# PowerFull_car_engineSteering.net
KiCad netlist of a schematic drawn in Altium Designer
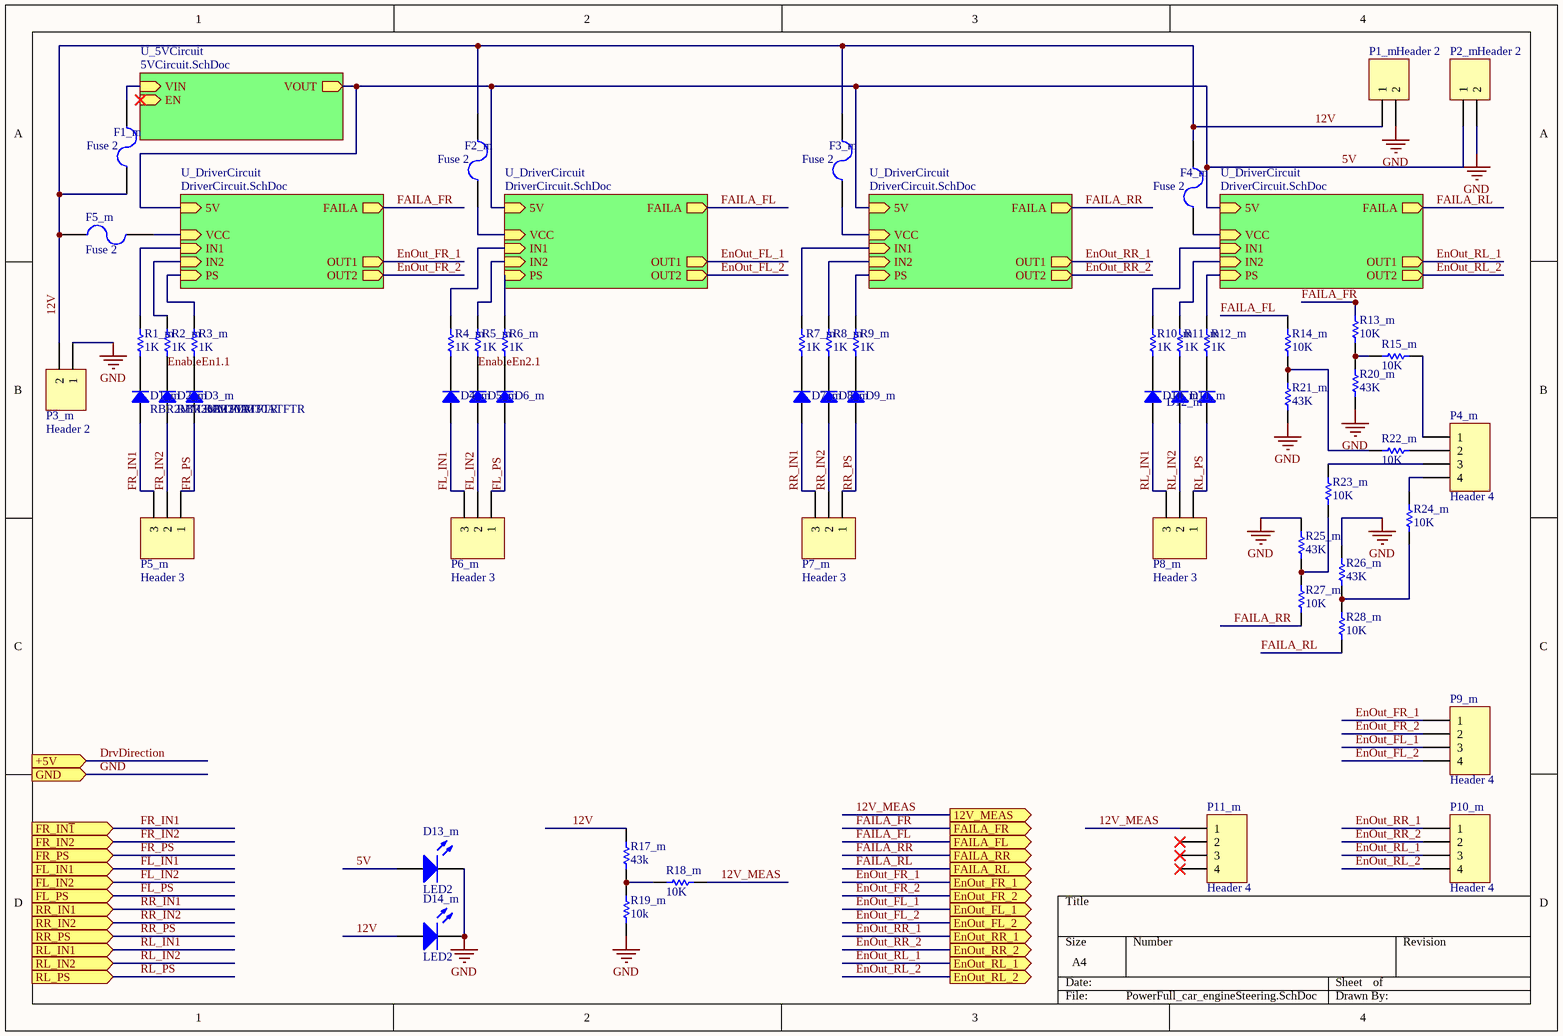
[diagram p0: PowerFull_car_engineSteering.SchDoc]

(export (version "E")
  (design (tool "Eeschema 10.0.6"))
  (components
    (comp (ref "D1_m")
      (value "RBR2MM30ATFTR")
      (footprint "SOD123F")
      (description "DIODE (RECTIFIER FRD) 30V-VR 2A-")
      (fields (field (name "MANUFACTURER") "Rohm Semiconductor"))
      (libsource (lib "Celestial Altium Library - altium_library (5)") (part "Diode"))
    )
    (comp (ref "D2_m")
      (value "RBR2MM30ATFTR")
      (footprint "SOD123F")
      (description "DIODE (RECTIFIER FRD) 30V-VR 2A-")
      (fields (field (name "MANUFACTURER") "Rohm Semiconductor"))
      (libsource (lib "Celestial Altium Library - altium_library (5)") (part "Diode"))
    )
    (comp (ref "D3_m")
      (value "RBR2MM30ATFTR")
      (footprint "SOD123F")
      (description "DIODE (RECTIFIER FRD) 30V-VR 2A-")
      (fields (field (name "MANUFACTURER") "Rohm Semiconductor"))
      (libsource (lib "Celestial Altium Library - altium_library (5)") (part "Diode"))
    )
    (comp (ref "D4_m")
      (value "RBR2MM30ATFTR")
      (footprint "SOD123F")
      (description "DIODE (RECTIFIER FRD) 30V-VR 2A-")
      (fields (field (name "MANUFACTURER") "Rohm Semiconductor"))
      (libsource (lib "Celestial Altium Library - altium_library (5)") (part "Diode"))
    )
    (comp (ref "D5_m")
      (value "RBR2MM30ATFTR")
      (footprint "SOD123F")
      (description "DIODE (RECTIFIER FRD) 30V-VR 2A-")
      (fields (field (name "MANUFACTURER") "Rohm Semiconductor"))
      (libsource (lib "Celestial Altium Library - altium_library (5)") (part "Diode"))
    )
    (comp (ref "D6_m")
      (value "RBR2MM30ATFTR")
      (footprint "SOD123F")
      (description "DIODE (RECTIFIER FRD) 30V-VR 2A-")
      (fields (field (name "MANUFACTURER") "Rohm Semiconductor"))
      (libsource (lib "Celestial Altium Library - altium_library (5)") (part "Diode"))
    )
    (comp (ref "D7_m")
      (value "RBR2MM30ATFTR")
      (footprint "SOD123F")
      (description "DIODE (RECTIFIER FRD) 30V-VR 2A-")
      (fields (field (name "MANUFACTURER") "Rohm Semiconductor"))
      (libsource (lib "Celestial Altium Library - altium_library (5)") (part "Diode"))
    )
    (comp (ref "D8_m")
      (value "RBR2MM30ATFTR")
      (footprint "SOD123F")
      (description "DIODE (RECTIFIER FRD) 30V-VR 2A-")
      (fields (field (name "MANUFACTURER") "Rohm Semiconductor"))
      (libsource (lib "Celestial Altium Library - altium_library (5)") (part "Diode"))
    )
    (comp (ref "D9_m")
      (value "RBR2MM30ATFTR")
      (footprint "SOD123F")
      (description "DIODE (RECTIFIER FRD) 30V-VR 2A-")
      (fields (field (name "MANUFACTURER") "Rohm Semiconductor"))
      (libsource (lib "Celestial Altium Library - altium_library (5)") (part "Diode"))
    )
    (comp (ref "D10_m")
      (value "RBR2MM30ATFTR")
      (footprint "SOD123F")
      (description "DIODE (RECTIFIER FRD) 30V-VR 2A-")
      (fields (field (name "MANUFACTURER") "Rohm Semiconductor"))
      (libsource (lib "Celestial Altium Library - altium_library (5)") (part "Diode"))
    )
    (comp (ref "D11_m")
      (value "RBR2MM30ATFTR")
      (footprint "SOD123F")
      (description "DIODE (RECTIFIER FRD) 30V-VR 2A-")
      (fields (field (name "MANUFACTURER") "Rohm Semiconductor"))
      (libsource (lib "Celestial Altium Library - altium_library (5)") (part "Diode"))
    )
    (comp (ref "D12_m")
      (value "RBR2MM30ATFTR")
      (footprint "SOD123F")
      (description "DIODE (RECTIFIER FRD) 30V-VR 2A-")
      (fields (field (name "MANUFACTURER") "Rohm Semiconductor"))
      (libsource (lib "Celestial Altium Library - altium_library (5)") (part "Diode"))
    )
    (comp (ref "D13_m")
      (value "LED2")
      (footprint "1608[0603]")
      (description "Typical RED, GREEN, YELLOW, AMBER GaAs LED")
      (fields (field (name "PUBLISHER") "Altium Limited"))
      (libsource (lib "Miscellaneous Devices") (part "LED2"))
    )
    (comp (ref "D14_m")
      (value "LED2")
      (footprint "1608[0603]")
      (description "Typical RED, GREEN, YELLOW, AMBER GaAs LED")
      (fields (field (name "PUBLISHER") "Altium Limited"))
      (libsource (lib "Miscellaneous Devices") (part "LED2"))
    )
    (comp (ref "F1_m")
      (value "Fuse 2")
      (footprint "1608[0603]")
      (description "Fuse")
      (fields (field (name "PUBLISHER") "Altium Limited"))
      (libsource (lib "Miscellaneous Devices") (part "Fuse 2"))
    )
    (comp (ref "F2_m")
      (value "Fuse 2")
      (footprint "1608[0603]")
      (description "Fuse")
      (fields (field (name "PUBLISHER") "Altium Limited"))
      (libsource (lib "Miscellaneous Devices") (part "Fuse 2"))
    )
    (comp (ref "F3_m")
      (value "Fuse 2")
      (footprint "1608[0603]")
      (description "Fuse")
      (fields (field (name "PUBLISHER") "Altium Limited"))
      (libsource (lib "Miscellaneous Devices") (part "Fuse 2"))
    )
    (comp (ref "F4_m")
      (value "Fuse 2")
      (footprint "1608[0603]")
      (description "Fuse")
      (fields (field (name "PUBLISHER") "Altium Limited"))
      (libsource (lib "Miscellaneous Devices") (part "Fuse 2"))
    )
    (comp (ref "F5_m")
      (value "Fuse 2")
      (footprint "1608[0603]")
      (description "Fuse")
      (fields (field (name "PUBLISHER") "Altium Limited"))
      (libsource (lib "Miscellaneous Devices") (part "Fuse 2"))
    )
    (comp (ref "P1_m")
      (value "Header 2")
      (footprint "HDR1X2")
      (description "Header, 2-Pin")
      (fields (field (name "PUBLISHER") "Altium Limited"))
      (libsource (lib "Miscellaneous Connectors") (part "Header 2"))
    )
    (comp (ref "P2_m")
      (value "Header 2")
      (footprint "HDR1X2")
      (description "Header, 2-Pin")
      (fields (field (name "PUBLISHER") "Altium Limited"))
      (libsource (lib "Miscellaneous Connectors") (part "Header 2"))
    )
    (comp (ref "P3_m")
      (value "Header 2")
      (footprint "HDR1X2")
      (description "Header, 2-Pin")
      (fields (field (name "PUBLISHER") "Altium Limited"))
      (libsource (lib "") (part "Header 2_1"))
    )
    (comp (ref "P4_m")
      (value "Header 4")
      (footprint "HDR1X4")
      (description "Header, 4-Pin")
      (fields (field (name "PUBLISHER") "Altium Limited"))
      (libsource (lib "Miscellaneous Connectors") (part "Header 4"))
    )
    (comp (ref "P5_m")
      (value "Header 3")
      (footprint "HDR1X3")
      (description "Header, 3-Pin")
      (fields (field (name "PUBLISHER") "Altium Limited"))
      (libsource (lib "Miscellaneous Connectors") (part "Header 3"))
    )
    (comp (ref "P6_m")
      (value "Header 3")
      (footprint "HDR1X3")
      (description "Header, 3-Pin")
      (fields (field (name "PUBLISHER") "Altium Limited"))
      (libsource (lib "Miscellaneous Connectors") (part "Header 3"))
    )
    (comp (ref "P7_m")
      (value "Header 3")
      (footprint "HDR1X3")
      (description "Header, 3-Pin")
      (fields (field (name "PUBLISHER") "Altium Limited"))
      (libsource (lib "Miscellaneous Connectors") (part "Header 3"))
    )
    (comp (ref "P8_m")
      (value "Header 3")
      (footprint "HDR1X3")
      (description "Header, 3-Pin")
      (fields (field (name "PUBLISHER") "Altium Limited"))
      (libsource (lib "Miscellaneous Connectors") (part "Header 3"))
    )
    (comp (ref "P9_m")
      (value "Header 4")
      (footprint "HDR1X4")
      (description "Header, 4-Pin")
      (fields (field (name "PUBLISHER") "Altium Limited"))
      (libsource (lib "Miscellaneous Connectors") (part "Header 4"))
    )
    (comp (ref "P10_m")
      (value "Header 4")
      (footprint "HDR1X4")
      (description "Header, 4-Pin")
      (fields (field (name "PUBLISHER") "Altium Limited"))
      (libsource (lib "Miscellaneous Connectors") (part "Header 4"))
    )
    (comp (ref "P11_m")
      (value "Header 4")
      (footprint "HDR1X4")
      (description "Header, 4-Pin")
      (fields (field (name "PUBLISHER") "Altium Limited"))
      (libsource (lib "Miscellaneous Connectors") (part "Header 4"))
    )
    (comp (ref "R1_m")
      (value "1K")
      (footprint "1608[0603]")
      (description "Resistor")
      (fields (field (name "Comment") "Res1") (field (name "PUBLISHER") "Altium Limited"))
      (libsource (lib "Miscellaneous Devices") (part "Res1"))
    )
    (comp (ref "R2_m")
      (value "1K")
      (footprint "1608[0603]")
      (description "Resistor")
      (fields (field (name "Comment") "Res1") (field (name "PUBLISHER") "Altium Limited"))
      (libsource (lib "Miscellaneous Devices") (part "Res1"))
    )
    (comp (ref "R3_m")
      (value "1K")
      (footprint "1608[0603]")
      (description "Resistor")
      (fields (field (name "Comment") "Res1") (field (name "PUBLISHER") "Altium Limited"))
      (libsource (lib "Miscellaneous Devices") (part "Res1"))
    )
    (comp (ref "R4_m")
      (value "1K")
      (footprint "1608[0603]")
      (description "Resistor")
      (fields (field (name "Comment") "Res1") (field (name "PUBLISHER") "Altium Limited"))
      (libsource (lib "Miscellaneous Devices") (part "Res1"))
    )
    (comp (ref "R5_m")
      (value "1K")
      (footprint "1608[0603]")
      (description "Resistor")
      (fields (field (name "Comment") "Res1") (field (name "PUBLISHER") "Altium Limited"))
      (libsource (lib "Miscellaneous Devices") (part "Res1"))
    )
    (comp (ref "R6_m")
      (value "1K")
      (footprint "1608[0603]")
      (description "Resistor")
      (fields (field (name "Comment") "Res1") (field (name "PUBLISHER") "Altium Limited"))
      (libsource (lib "Miscellaneous Devices") (part "Res1"))
    )
    (comp (ref "R7_m")
      (value "1K")
      (footprint "1608[0603]")
      (description "Resistor")
      (fields (field (name "Comment") "Res1") (field (name "PUBLISHER") "Altium Limited"))
      (libsource (lib "Miscellaneous Devices") (part "Res1"))
    )
    (comp (ref "R8_m")
      (value "1K")
      (footprint "1608[0603]")
      (description "Resistor")
      (fields (field (name "Comment") "Res1") (field (name "PUBLISHER") "Altium Limited"))
      (libsource (lib "Miscellaneous Devices") (part "Res1"))
    )
    (comp (ref "R9_m")
      (value "1K")
      (footprint "1608[0603]")
      (description "Resistor")
      (fields (field (name "Comment") "Res1") (field (name "PUBLISHER") "Altium Limited"))
      (libsource (lib "Miscellaneous Devices") (part "Res1"))
    )
    (comp (ref "R10_m")
      (value "1K")
      (footprint "1608[0603]")
      (description "Resistor")
      (fields (field (name "Comment") "Res1") (field (name "PUBLISHER") "Altium Limited"))
      (libsource (lib "Miscellaneous Devices") (part "Res1"))
    )
    (comp (ref "R11_m")
      (value "1K")
      (footprint "1608[0603]")
      (description "Resistor")
      (fields (field (name "Comment") "Res1") (field (name "PUBLISHER") "Altium Limited"))
      (libsource (lib "Miscellaneous Devices") (part "Res1"))
    )
    (comp (ref "R12_m")
      (value "1K")
      (footprint "1608[0603]")
      (description "Resistor")
      (fields (field (name "Comment") "Res1") (field (name "PUBLISHER") "Altium Limited"))
      (libsource (lib "Miscellaneous Devices") (part "Res1"))
    )
    (comp (ref "R13_m")
      (value "10K")
      (footprint "1608[0603]")
      (description "Resistor")
      (fields (field (name "Comment") "Res1") (field (name "PUBLISHER") "Altium Limited"))
      (libsource (lib "Miscellaneous Devices") (part "Res1"))
    )
    (comp (ref "R14_m")
      (value "10K")
      (footprint "1608[0603]")
      (description "Resistor")
      (fields (field (name "Comment") "Res1") (field (name "PUBLISHER") "Altium Limited"))
      (libsource (lib "Miscellaneous Devices") (part "Res1"))
    )
    (comp (ref "R15_m")
      (value "10K")
      (footprint "1608[0603]")
      (description "Resistor")
      (fields (field (name "Comment") "Res1") (field (name "PUBLISHER") "Altium Limited"))
      (libsource (lib "Miscellaneous Devices") (part "Res1"))
    )
    (comp (ref "R17_m")
      (value "43k")
      (footprint "1608[0603]")
      (description "Resistor")
      (fields (field (name "Comment") "Res1") (field (name "PUBLISHER") "Altium Limited"))
      (libsource (lib "Miscellaneous Devices") (part "Res1"))
    )
    (comp (ref "R18_m")
      (value "10K")
      (footprint "1608[0603]")
      (description "Resistor")
      (fields (field (name "Comment") "Res1") (field (name "PUBLISHER") "Altium Limited"))
      (libsource (lib "Miscellaneous Devices") (part "Res1"))
    )
    (comp (ref "R19_m")
      (value "10k")
      (footprint "1608[0603]")
      (description "Resistor")
      (fields (field (name "Comment") "Res1") (field (name "PUBLISHER") "Altium Limited"))
      (libsource (lib "Miscellaneous Devices") (part "Res1"))
    )
    (comp (ref "R20_m")
      (value "43K")
      (footprint "1608[0603]")
      (description "Resistor")
      (fields (field (name "Comment") "Res1") (field (name "PUBLISHER") "Altium Limited"))
      (libsource (lib "Miscellaneous Devices") (part "Res1"))
    )
    (comp (ref "R21_m")
      (value "43K")
      (footprint "1608[0603]")
      (description "Resistor")
      (fields (field (name "Comment") "Res1") (field (name "PUBLISHER") "Altium Limited"))
      (libsource (lib "Miscellaneous Devices") (part "Res1"))
    )
    (comp (ref "R22_m")
      (value "10K")
      (footprint "1608[0603]")
      (description "Resistor")
      (fields (field (name "Comment") "Res1") (field (name "PUBLISHER") "Altium Limited"))
      (libsource (lib "Miscellaneous Devices") (part "Res1"))
    )
    (comp (ref "R23_m")
      (value "10K")
      (footprint "1608[0603]")
      (description "Resistor")
      (fields (field (name "Comment") "Res1") (field (name "PUBLISHER") "Altium Limited"))
      (libsource (lib "Miscellaneous Devices") (part "Res1"))
    )
    (comp (ref "R24_m")
      (value "10K")
      (footprint "1608[0603]")
      (description "Resistor")
      (fields (field (name "Comment") "Res1") (field (name "PUBLISHER") "Altium Limited"))
      (libsource (lib "Miscellaneous Devices") (part "Res1"))
    )
    (comp (ref "R25_m")
      (value "43K")
      (footprint "1608[0603]")
      (description "Resistor")
      (fields (field (name "Comment") "Res1") (field (name "PUBLISHER") "Altium Limited"))
      (libsource (lib "Miscellaneous Devices") (part "Res1"))
    )
    (comp (ref "R26_m")
      (value "43K")
      (footprint "1608[0603]")
      (description "Resistor")
      (fields (field (name "Comment") "Res1") (field (name "PUBLISHER") "Altium Limited"))
      (libsource (lib "Miscellaneous Devices") (part "Res1"))
    )
    (comp (ref "R27_m")
      (value "10K")
      (footprint "1608[0603]")
      (description "Resistor")
      (fields (field (name "Comment") "Res1") (field (name "PUBLISHER") "Altium Limited"))
      (libsource (lib "Miscellaneous Devices") (part "Res1"))
    )
    (comp (ref "R28_m")
      (value "10K")
      (footprint "1608[0603]")
      (description "Resistor")
      (fields (field (name "Comment") "Res1") (field (name "PUBLISHER") "Altium Limited"))
      (libsource (lib "Miscellaneous Devices") (part "Res1"))
    )
  )
  (nets
    (net (code "1") (name "/5V") (class "Default")
      (node (ref "D13_m") (pin "1") (pinfunction "A_1") (pintype "passive"))
      (node (ref "P2_m") (pin "1") (pinfunction "1_1") (pintype "passive"))
    )
    (net (code "2") (name "/12V") (class "Default")
      (node (ref "D14_m") (pin "1") (pinfunction "A_1") (pintype "passive"))
      (node (ref "F1_m") (pin "1") (pinfunction "1_1") (pintype "passive"))
      (node (ref "F2_m") (pin "2") (pinfunction "2_2") (pintype "passive"))
      (node (ref "F3_m") (pin "2") (pinfunction "2_2") (pintype "passive"))
      (node (ref "F4_m") (pin "2") (pinfunction "2_2") (pintype "passive"))
      (node (ref "F5_m") (pin "2") (pinfunction "2_2") (pintype "passive"))
      (node (ref "P1_m") (pin "1") (pinfunction "1_1") (pintype "passive"))
      (node (ref "P3_m") (pin "2") (pinfunction "2_2") (pintype "passive"))
      (node (ref "R17_m") (pin "2") (pinfunction "2_2") (pintype "passive"))
    )
    (net (code "3") (name "/12V_MEAS") (class "Default")
      (node (ref "P11_m") (pin "1") (pinfunction "1_1") (pintype "passive"))
      (node (ref "R18_m") (pin "1") (pinfunction "1_1") (pintype "passive"))
    )
    (net (code "6") (name "/EnOut_FL_1") (class "Default")
      (node (ref "P9_m") (pin "3") (pinfunction "3_3") (pintype "passive"))
    )
    (net (code "7") (name "/EnOut_FL_2") (class "Default")
      (node (ref "P9_m") (pin "4") (pinfunction "4_4") (pintype "passive"))
    )
    (net (code "8") (name "/EnOut_FR_1") (class "Default")
      (node (ref "P9_m") (pin "1") (pinfunction "1_1") (pintype "passive"))
    )
    (net (code "9") (name "/EnOut_FR_2") (class "Default")
      (node (ref "P9_m") (pin "2") (pinfunction "2_2") (pintype "passive"))
    )
    (net (code "10") (name "/EnOut_RL_1") (class "Default")
      (node (ref "P10_m") (pin "3") (pinfunction "3_3") (pintype "passive"))
    )
    (net (code "11") (name "/EnOut_RL_2") (class "Default")
      (node (ref "P10_m") (pin "4") (pinfunction "4_4") (pintype "passive"))
    )
    (net (code "12") (name "/EnOut_RR_1") (class "Default")
      (node (ref "P10_m") (pin "1") (pinfunction "1_1") (pintype "passive"))
    )
    (net (code "13") (name "/EnOut_RR_2") (class "Default")
      (node (ref "P10_m") (pin "2") (pinfunction "2_2") (pintype "passive"))
    )
    (net (code "14") (name "/EnableEn1.1") (class "Default")
      (node (ref "D2_m") (pin "2") (pinfunction "2_2") (pintype "passive"))
      (node (ref "R2_m") (pin "1") (pinfunction "1_1") (pintype "passive"))
    )
    (net (code "15") (name "/EnableEn2.1") (class "Default")
      (node (ref "D5_m") (pin "2") (pinfunction "2_2") (pintype "passive"))
      (node (ref "R5_m") (pin "1") (pinfunction "1_1") (pintype "passive"))
    )
    (net (code "16") (name "/FAILA_FL") (class "Default")
      (node (ref "R14_m") (pin "2") (pinfunction "2_2") (pintype "passive"))
    )
    (net (code "17") (name "/FAILA_FR") (class "Default")
      (node (ref "R13_m") (pin "2") (pinfunction "2_2") (pintype "passive"))
    )
    (net (code "18") (name "/FAILA_RL") (class "Default")
      (node (ref "R28_m") (pin "1") (pinfunction "1_1") (pintype "passive"))
    )
    (net (code "19") (name "/FAILA_RR") (class "Default")
      (node (ref "R27_m") (pin "1") (pinfunction "1_1") (pintype "passive"))
    )
    (net (code "20") (name "/FL_IN1") (class "Default")
      (node (ref "D4_m") (pin "1") (pinfunction "1_1") (pintype "passive"))
      (node (ref "P6_m") (pin "3") (pinfunction "3_3") (pintype "passive"))
    )
    (net (code "21") (name "/FL_IN2") (class "Default")
      (node (ref "D5_m") (pin "1") (pinfunction "1_1") (pintype "passive"))
      (node (ref "P6_m") (pin "2") (pinfunction "2_2") (pintype "passive"))
    )
    (net (code "22") (name "/FL_PS") (class "Default")
      (node (ref "D6_m") (pin "1") (pinfunction "1_1") (pintype "passive"))
      (node (ref "P6_m") (pin "1") (pinfunction "1_1") (pintype "passive"))
    )
    (net (code "23") (name "/FR_IN1") (class "Default")
      (node (ref "D1_m") (pin "1") (pinfunction "1_1") (pintype "passive"))
      (node (ref "P5_m") (pin "3") (pinfunction "3_3") (pintype "passive"))
    )
    (net (code "24") (name "/FR_IN2") (class "Default")
      (node (ref "D2_m") (pin "1") (pinfunction "1_1") (pintype "passive"))
      (node (ref "P5_m") (pin "2") (pinfunction "2_2") (pintype "passive"))
    )
    (net (code "25") (name "/FR_PS") (class "Default")
      (node (ref "D3_m") (pin "1") (pinfunction "1_1") (pintype "passive"))
      (node (ref "P5_m") (pin "1") (pinfunction "1_1") (pintype "passive"))
    )
    (net (code "26") (name "/IN1") (class "Default")
      (node (ref "R1_m") (pin "2") (pinfunction "2_2") (pintype "passive"))
    )
    (net (code "27") (name "/IN1_1") (class "Default")
      (node (ref "R7_m") (pin "2") (pinfunction "2_2") (pintype "passive"))
    )
    (net (code "28") (name "/IN1_2") (class "Default")
      (node (ref "R10_m") (pin "2") (pinfunction "2_2") (pintype "passive"))
    )
    (net (code "29") (name "/IN1_3") (class "Default")
      (node (ref "R4_m") (pin "2") (pinfunction "2_2") (pintype "passive"))
    )
    (net (code "30") (name "/IN2") (class "Default")
      (node (ref "R2_m") (pin "2") (pinfunction "2_2") (pintype "passive"))
    )
    (net (code "31") (name "/IN2_1") (class "Default")
      (node (ref "R8_m") (pin "2") (pinfunction "2_2") (pintype "passive"))
    )
    (net (code "32") (name "/IN2_2") (class "Default")
      (node (ref "R11_m") (pin "2") (pinfunction "2_2") (pintype "passive"))
    )
    (net (code "33") (name "/IN2_3") (class "Default")
      (node (ref "R5_m") (pin "2") (pinfunction "2_2") (pintype "passive"))
    )
    (net (code "34") (name "/PS") (class "Default")
      (node (ref "R3_m") (pin "2") (pinfunction "2_2") (pintype "passive"))
    )
    (net (code "35") (name "/PS_1") (class "Default")
      (node (ref "R9_m") (pin "2") (pinfunction "2_2") (pintype "passive"))
    )
    (net (code "36") (name "/PS_2") (class "Default")
      (node (ref "R12_m") (pin "2") (pinfunction "2_2") (pintype "passive"))
    )
    (net (code "37") (name "/PS_3") (class "Default")
      (node (ref "R6_m") (pin "2") (pinfunction "2_2") (pintype "passive"))
    )
    (net (code "38") (name "/RL_IN1") (class "Default")
      (node (ref "D10_m") (pin "1") (pinfunction "1_1") (pintype "passive"))
      (node (ref "P8_m") (pin "3") (pinfunction "3_3") (pintype "passive"))
    )
    (net (code "39") (name "/RL_IN2") (class "Default")
      (node (ref "D11_m") (pin "1") (pinfunction "1_1") (pintype "passive"))
      (node (ref "P8_m") (pin "2") (pinfunction "2_2") (pintype "passive"))
    )
    (net (code "40") (name "/RL_PS") (class "Default")
      (node (ref "D12_m") (pin "1") (pinfunction "1_1") (pintype "passive"))
      (node (ref "P8_m") (pin "1") (pinfunction "1_1") (pintype "passive"))
    )
    (net (code "41") (name "/RR_IN1") (class "Default")
      (node (ref "D7_m") (pin "1") (pinfunction "1_1") (pintype "passive"))
      (node (ref "P7_m") (pin "3") (pinfunction "3_3") (pintype "passive"))
    )
    (net (code "42") (name "/RR_IN2") (class "Default")
      (node (ref "D8_m") (pin "1") (pinfunction "1_1") (pintype "passive"))
      (node (ref "P7_m") (pin "2") (pinfunction "2_2") (pintype "passive"))
    )
    (net (code "43") (name "/RR_PS") (class "Default")
      (node (ref "D9_m") (pin "1") (pinfunction "1_1") (pintype "passive"))
      (node (ref "P7_m") (pin "1") (pinfunction "1_1") (pintype "passive"))
    )
    (net (code "44") (name "/VCC") (class "Default")
      (node (ref "F5_m") (pin "1") (pinfunction "1_1") (pintype "passive"))
    )
    (net (code "45") (name "/VCC_1") (class "Default")
      (node (ref "F3_m") (pin "1") (pinfunction "1_1") (pintype "passive"))
    )
    (net (code "46") (name "/VCC_2") (class "Default")
      (node (ref "F4_m") (pin "1") (pinfunction "1_1") (pintype "passive"))
    )
    (net (code "47") (name "/VCC_3") (class "Default")
      (node (ref "F2_m") (pin "1") (pinfunction "1_1") (pintype "passive"))
    )
    (net (code "48") (name "/VIN") (class "Default")
      (node (ref "F1_m") (pin "2") (pinfunction "2_2") (pintype "passive"))
    )
    (net (code "49") (name "GND") (class "Default")
      (node (ref "D13_m") (pin "2") (pinfunction "K_2") (pintype "passive"))
      (node (ref "D14_m") (pin "2") (pinfunction "K_2") (pintype "passive"))
      (node (ref "P1_m") (pin "2") (pinfunction "2_2") (pintype "passive"))
      (node (ref "P2_m") (pin "2") (pinfunction "2_2") (pintype "passive"))
      (node (ref "P3_m") (pin "1") (pinfunction "1_1") (pintype "passive"))
      (node (ref "R19_m") (pin "1") (pinfunction "1_1") (pintype "passive"))
      (node (ref "R20_m") (pin "1") (pinfunction "1_1") (pintype "passive"))
      (node (ref "R21_m") (pin "1") (pinfunction "1_1") (pintype "passive"))
      (node (ref "R25_m") (pin "2") (pinfunction "2_2") (pintype "passive"))
      (node (ref "R26_m") (pin "2") (pinfunction "2_2") (pintype "passive"))
    )
    (net (code "50") (name "Net-(D1_m-Pad2)") (class "Default")
      (node (ref "D1_m") (pin "2") (pinfunction "2_2") (pintype "passive"))
      (node (ref "R1_m") (pin "1") (pinfunction "1_1") (pintype "passive"))
    )
    (net (code "51") (name "Net-(D3_m-Pad2)") (class "Default")
      (node (ref "D3_m") (pin "2") (pinfunction "2_2") (pintype "passive"))
      (node (ref "R3_m") (pin "1") (pinfunction "1_1") (pintype "passive"))
    )
    (net (code "52") (name "Net-(D4_m-Pad2)") (class "Default")
      (node (ref "D4_m") (pin "2") (pinfunction "2_2") (pintype "passive"))
      (node (ref "R4_m") (pin "1") (pinfunction "1_1") (pintype "passive"))
    )
    (net (code "53") (name "Net-(D6_m-Pad2)") (class "Default")
      (node (ref "D6_m") (pin "2") (pinfunction "2_2") (pintype "passive"))
      (node (ref "R6_m") (pin "1") (pinfunction "1_1") (pintype "passive"))
    )
    (net (code "54") (name "Net-(D7_m-Pad2)") (class "Default")
      (node (ref "D7_m") (pin "2") (pinfunction "2_2") (pintype "passive"))
      (node (ref "R7_m") (pin "1") (pinfunction "1_1") (pintype "passive"))
    )
    (net (code "55") (name "Net-(D8_m-Pad2)") (class "Default")
      (node (ref "D8_m") (pin "2") (pinfunction "2_2") (pintype "passive"))
      (node (ref "R8_m") (pin "1") (pinfunction "1_1") (pintype "passive"))
    )
    (net (code "56") (name "Net-(D9_m-Pad2)") (class "Default")
      (node (ref "D9_m") (pin "2") (pinfunction "2_2") (pintype "passive"))
      (node (ref "R9_m") (pin "1") (pinfunction "1_1") (pintype "passive"))
    )
    (net (code "57") (name "Net-(D10_m-Pad2)") (class "Default")
      (node (ref "D10_m") (pin "2") (pinfunction "2_2") (pintype "passive"))
      (node (ref "R10_m") (pin "1") (pinfunction "1_1") (pintype "passive"))
    )
    (net (code "58") (name "Net-(D11_m-Pad2)") (class "Default")
      (node (ref "D11_m") (pin "2") (pinfunction "2_2") (pintype "passive"))
      (node (ref "R11_m") (pin "1") (pinfunction "1_1") (pintype "passive"))
    )
    (net (code "59") (name "Net-(D12_m-Pad2)") (class "Default")
      (node (ref "D12_m") (pin "2") (pinfunction "2_2") (pintype "passive"))
      (node (ref "R12_m") (pin "1") (pinfunction "1_1") (pintype "passive"))
    )
    (net (code "60") (name "Net-(P4_m-Pad1)") (class "Default")
      (node (ref "P4_m") (pin "1") (pinfunction "1_1") (pintype "passive"))
      (node (ref "R15_m") (pin "1") (pinfunction "1_1") (pintype "passive"))
    )
    (net (code "61") (name "Net-(P4_m-Pad2)") (class "Default")
      (node (ref "P4_m") (pin "2") (pinfunction "2_2") (pintype "passive"))
      (node (ref "R22_m") (pin "1") (pinfunction "1_1") (pintype "passive"))
    )
    (net (code "62") (name "Net-(P4_m-Pad3)") (class "Default")
      (node (ref "P4_m") (pin "3") (pinfunction "3_3") (pintype "passive"))
      (node (ref "R23_m") (pin "1") (pinfunction "1_1") (pintype "passive"))
    )
    (net (code "63") (name "Net-(P4_m-Pad4)") (class "Default")
      (node (ref "P4_m") (pin "4") (pinfunction "4_4") (pintype "passive"))
      (node (ref "R24_m") (pin "1") (pinfunction "1_1") (pintype "passive"))
    )
    (net (code "64") (name "Net-(R13_m-Pad1)") (class "Default")
      (node (ref "R13_m") (pin "1") (pinfunction "1_1") (pintype "passive"))
      (node (ref "R15_m") (pin "2") (pinfunction "2_2") (pintype "passive"))
      (node (ref "R20_m") (pin "2") (pinfunction "2_2") (pintype "passive"))
    )
    (net (code "65") (name "Net-(R14_m-Pad1)") (class "Default")
      (node (ref "R14_m") (pin "1") (pinfunction "1_1") (pintype "passive"))
      (node (ref "R21_m") (pin "2") (pinfunction "2_2") (pintype "passive"))
      (node (ref "R22_m") (pin "2") (pinfunction "2_2") (pintype "passive"))
    )
    (net (code "66") (name "Net-(R17_m-Pad1)") (class "Default")
      (node (ref "R17_m") (pin "1") (pinfunction "1_1") (pintype "passive"))
      (node (ref "R18_m") (pin "2") (pinfunction "2_2") (pintype "passive"))
      (node (ref "R19_m") (pin "2") (pinfunction "2_2") (pintype "passive"))
    )
    (net (code "67") (name "Net-(R23_m-Pad2)") (class "Default")
      (node (ref "R23_m") (pin "2") (pinfunction "2_2") (pintype "passive"))
      (node (ref "R25_m") (pin "1") (pinfunction "1_1") (pintype "passive"))
      (node (ref "R27_m") (pin "2") (pinfunction "2_2") (pintype "passive"))
    )
    (net (code "68") (name "Net-(R24_m-Pad2)") (class "Default")
      (node (ref "R24_m") (pin "2") (pinfunction "2_2") (pintype "passive"))
      (node (ref "R26_m") (pin "1") (pinfunction "1_1") (pintype "passive"))
      (node (ref "R28_m") (pin "2") (pinfunction "2_2") (pintype "passive"))
    )
    (net (code "69") (name "unconnected-(P11_m-Pad2)") (class "Default")
      (node (ref "P11_m") (pin "2") (pinfunction "2_2") (pintype "passive+no_connect"))
    )
    (net (code "70") (name "unconnected-(P11_m-Pad3)") (class "Default")
      (node (ref "P11_m") (pin "3") (pinfunction "3_3") (pintype "passive+no_connect"))
    )
    (net (code "71") (name "unconnected-(P11_m-Pad4)") (class "Default")
      (node (ref "P11_m") (pin "4") (pinfunction "4_4") (pintype "passive+no_connect"))
    )
  )
)
